# 03_ESP32.net
KiCad netlist of a schematic drawn in Altium Designer
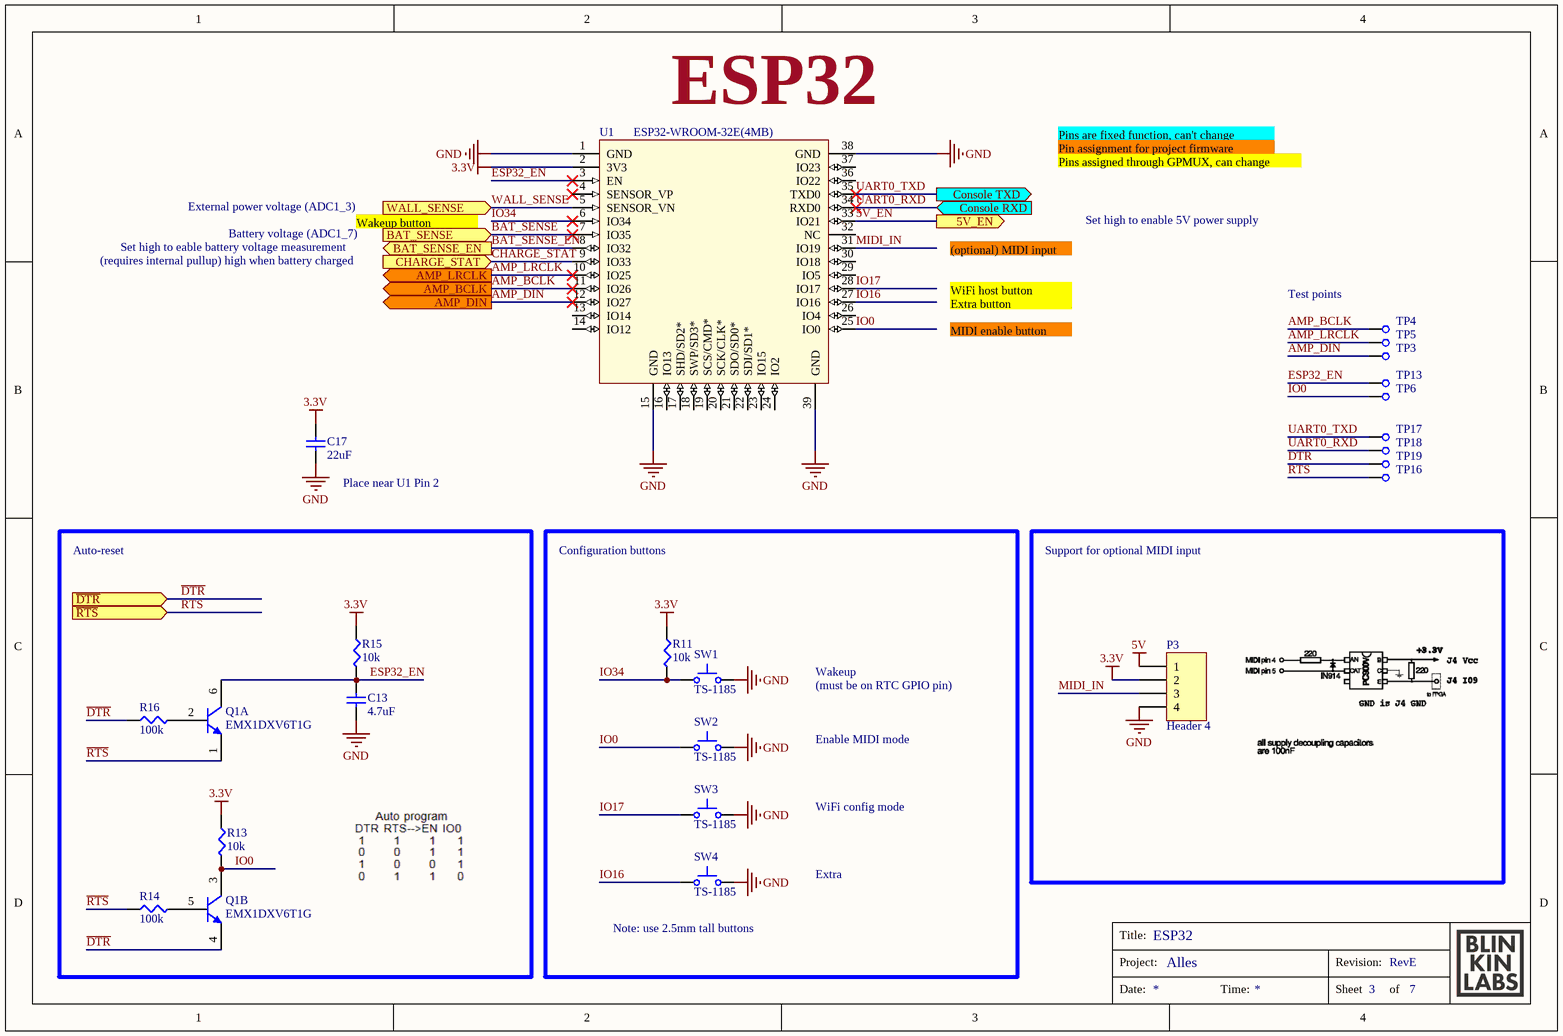
[diagram p0: [03] ESP32.SchDoc]

(export (version "E")
  (design (tool "Eeschema 10.0.6"))
  (components
    (comp (ref "C13")
      (value "4.7uF")
      (footprint "CAPC1608X09L")
      (description "CAP CER 4.7UF 10V X5R 0603")
      (fields
        (field (name "PARTNUMBER") "GRM185R61A475KE11D")
        (field (name "DIGI-KEY PART NUMBER") "490-11988-1-ND")
      )
      (libsource (lib "cap_murata") (part "CAPACITOR"))
    )
    (comp (ref "C17")
      (value "22uF")
      (footprint "CAPC1608X09L")
      (description "CAP CER 22UF 10V X5R 0603")
      (fields
        (field (name "PARTNUMBER") "GRM187R61A226ME15D")
        (field (name "DIGI-KEY PART NUMBER") "490-13243-1-ND")
      )
      (libsource (lib "cap_murata") (part "CAPACITOR"))
    )
    (comp (ref "P3")
      (value "Header 4")
      (footprint "HDR1X4")
      (description "Header, 4-Pin")
      (fields (field (name "PUBLISHER") "Altium Limited"))
      (libsource (lib "Miscellaneous Connectors") (part "Header 4"))
    )
    (comp (ref "Q1")
      (value "EMX1DXV6T1G")
      (footprint "ONSC-SOT-563-6-463A-01_V")
      (description "Dual NPN General Purpose Amplifier Transistors, 6-Pin SOT-563, Pb-Free, Tape and Reel")
      (fields (field (name "MANUFACTURER") "On Semiconductor"))
      (libsource (lib "Altium Content Vault") (part "ONSC-NPN_NPN-6_E"))
    )
    (comp (ref "R11")
      (value "10k")
      (footprint "ERJ2G(0402)_L")
      (description "RES SMD 10K OHM 5% 1/10W 0402")
      (fields (field (name "PARTNUMBER") "ERJ-2GEJ103X") (field (name "DIGI-KEY PART NUMBER") "P10KJCT-ND"))
      (libsource (lib "res_panasonic_erj_xls") (part "RESISTOR"))
    )
    (comp (ref "R13")
      (value "10k")
      (footprint "ERJ2G(0402)_L")
      (description "RES SMD 10K OHM 5% 1/10W 0402")
      (fields (field (name "PARTNUMBER") "ERJ-2GEJ103X") (field (name "DIGI-KEY PART NUMBER") "P10KJCT-ND"))
      (libsource (lib "res_panasonic_erj_xls") (part "RESISTOR"))
    )
    (comp (ref "R14")
      (value "100k")
      (footprint "ERJ2G(0402)_L")
      (description "RES SMD 100K OHM 5% 1/10W 0402")
      (fields (field (name "PARTNUMBER") "ERJ-2GEJ104X") (field (name "DIGI-KEY PART NUMBER") "P100KJCT-ND"))
      (libsource (lib "res_panasonic_erj_xls") (part "RESISTOR"))
    )
    (comp (ref "R15")
      (value "10k")
      (footprint "ERJ2G(0402)_L")
      (description "RES SMD 10K OHM 5% 1/10W 0402")
      (fields (field (name "PARTNUMBER") "ERJ-2GEJ103X") (field (name "DIGI-KEY PART NUMBER") "P10KJCT-ND"))
      (libsource (lib "res_panasonic_erj_xls") (part "RESISTOR"))
    )
    (comp (ref "R16")
      (value "100k")
      (footprint "ERJ2G(0402)_L")
      (description "RES SMD 100K OHM 5% 1/10W 0402")
      (fields (field (name "PARTNUMBER") "ERJ-2GEJ104X") (field (name "DIGI-KEY PART NUMBER") "P100KJCT-ND"))
      (libsource (lib "res_panasonic_erj_xls") (part "RESISTOR"))
    )
    (comp (ref "SW1")
      (value "TS-1185")
      (footprint "TS-1185")
      (description "Tact Switch, 3x4mm, no alignment pin, turtle style")
      (fields (field (name "MANUFACTURER") "XKB"))
      (libsource (lib "Blinkinlabs") (part "TS-1185"))
    )
    (comp (ref "SW2")
      (value "TS-1185")
      (footprint "TS-1185")
      (description "Tact Switch, 3x4mm, no alignment pin, turtle style")
      (fields (field (name "MANUFACTURER") "XKB"))
      (libsource (lib "Blinkinlabs") (part "TS-1185"))
    )
    (comp (ref "SW3")
      (value "TS-1185")
      (footprint "TS-1185")
      (description "Tact Switch, 3x4mm, no alignment pin, turtle style")
      (fields (field (name "MANUFACTURER") "XKB"))
      (libsource (lib "Blinkinlabs") (part "TS-1185"))
    )
    (comp (ref "SW4")
      (value "TS-1185")
      (footprint "TS-1185")
      (description "Tact Switch, 3x4mm, no alignment pin, turtle style")
      (fields (field (name "MANUFACTURER") "XKB"))
      (libsource (lib "Blinkinlabs") (part "TS-1185"))
    )
    (comp (ref "TP3")
      (value "TEST_POINT")
      (footprint "TP-SMD-1mm")
      (description "Test point")
      (libsource (lib "Blinkinlabs") (part "TEST_POINT"))
    )
    (comp (ref "TP4")
      (value "TEST_POINT")
      (footprint "TP-SMD-1mm")
      (description "Test point")
      (libsource (lib "Blinkinlabs") (part "TEST_POINT"))
    )
    (comp (ref "TP5")
      (value "TEST_POINT")
      (footprint "TP-SMD-1mm")
      (description "Test point")
      (libsource (lib "Blinkinlabs") (part "TEST_POINT"))
    )
    (comp (ref "TP6")
      (value "TEST_POINT")
      (footprint "TP-SMD-1mm")
      (description "Test point")
      (libsource (lib "Blinkinlabs") (part "TEST_POINT"))
    )
    (comp (ref "TP13")
      (value "TEST_POINT")
      (footprint "TP-SMD-1mm")
      (description "Test point")
      (libsource (lib "Blinkinlabs") (part "TEST_POINT"))
    )
    (comp (ref "TP16")
      (value "TEST_POINT")
      (footprint "TP-SMD-1mm")
      (description "Test point")
      (libsource (lib "Blinkinlabs") (part "TEST_POINT"))
    )
    (comp (ref "TP17")
      (value "TEST_POINT")
      (footprint "TP-SMD-1mm")
      (description "Test point")
      (libsource (lib "Blinkinlabs") (part "TEST_POINT"))
    )
    (comp (ref "TP18")
      (value "TEST_POINT")
      (footprint "TP-SMD-1mm")
      (description "Test point")
      (libsource (lib "Blinkinlabs") (part "TEST_POINT"))
    )
    (comp (ref "TP19")
      (value "TEST_POINT")
      (footprint "TP-SMD-1mm")
      (description "Test point")
      (libsource (lib "Blinkinlabs") (part "TEST_POINT"))
    )
    (comp (ref "U1")
      (value "ESP32-WROOM-32E(4MB)")
      (footprint "ESP32-WROOM-32-shortpad")
      (description "32-bit MCU & 2.4 GHz Wi-Fi & Bluetooth/Bluetooth LE")
      (fields (field (name "MANUFACTURER") "Espressif Systems") (field (name "LCSC PARTNUMBER") "C701341"))
      (libsource (lib "Blinkinlabs") (part "ESP32-WROOM-32E(4MB)"))
    )
  )
  (nets
    (net (code "1") (name "/5V_EN") (class "Default")
      (node (ref "U1") (pin "33") (pinfunction "IO21_33") (pintype "bidirectional"))
    )
    (net (code "2") (name "/AMP_BCLK") (class "Default")
      (node (ref "TP4") (pin "1") (pinfunction "TP_1") (pintype "passive"))
      (node (ref "U1") (pin "11") (pinfunction "IO26_11") (pintype "bidirectional"))
    )
    (net (code "3") (name "/AMP_DIN") (class "Default")
      (node (ref "TP3") (pin "1") (pinfunction "TP_1") (pintype "passive"))
      (node (ref "U1") (pin "12") (pinfunction "IO27_12") (pintype "bidirectional"))
    )
    (net (code "4") (name "/AMP_LRCLK") (class "Default")
      (node (ref "TP5") (pin "1") (pinfunction "TP_1") (pintype "passive"))
      (node (ref "U1") (pin "10") (pinfunction "IO25_10") (pintype "bidirectional"))
    )
    (net (code "5") (name "/BAT_SENSE") (class "Default")
      (node (ref "U1") (pin "7") (pinfunction "IO35_7") (pintype "input+no_connect"))
    )
    (net (code "6") (name "/BAT_SENSE_EN") (class "Default")
      (node (ref "U1") (pin "8") (pinfunction "IO32_8") (pintype "bidirectional"))
    )
    (net (code "7") (name "/CHARGE_STAT") (class "Default")
      (node (ref "U1") (pin "9") (pinfunction "IO33_9") (pintype "bidirectional"))
    )
    (net (code "8") (name "/ESP32_EN") (class "Default")
      (node (ref "C13") (pin "1") (pinfunction "1_1") (pintype "passive"))
      (node (ref "Q1") (pin "6") (pinfunction "C_6") (pintype "passive"))
      (node (ref "R15") (pin "2") (pinfunction "2_2") (pintype "passive"))
      (node (ref "TP13") (pin "1") (pinfunction "TP_1") (pintype "passive"))
      (node (ref "U1") (pin "3") (pinfunction "EN_3") (pintype "input"))
    )
    (net (code "9") (name "/IO0") (class "Default")
      (node (ref "Q1") (pin "3") (pinfunction "C_3") (pintype "passive"))
      (node (ref "R13") (pin "2") (pinfunction "2_2") (pintype "passive"))
      (node (ref "SW2") (pin "1") (pinfunction "1_1") (pintype "passive"))
      (node (ref "TP6") (pin "1") (pinfunction "TP_1") (pintype "passive"))
      (node (ref "U1") (pin "25") (pinfunction "IO0_25") (pintype "bidirectional"))
    )
    (net (code "10") (name "/IO16") (class "Default")
      (node (ref "SW4") (pin "1") (pinfunction "1_1") (pintype "passive"))
      (node (ref "U1") (pin "27") (pinfunction "IO16_27") (pintype "bidirectional"))
    )
    (net (code "11") (name "/IO17") (class "Default")
      (node (ref "SW3") (pin "1") (pinfunction "1_1") (pintype "passive"))
      (node (ref "U1") (pin "28") (pinfunction "IO17_28") (pintype "bidirectional"))
    )
    (net (code "12") (name "/IO34") (class "Default")
      (node (ref "R11") (pin "2") (pinfunction "2_2") (pintype "passive"))
      (node (ref "SW1") (pin "1") (pinfunction "1_1") (pintype "passive"))
      (node (ref "U1") (pin "6") (pinfunction "IO34_6") (pintype "input"))
    )
    (net (code "13") (name "/MIDI_IN") (class "Default")
      (node (ref "P3") (pin "3") (pinfunction "3_3") (pintype "passive"))
      (node (ref "U1") (pin "31") (pinfunction "IO19_31") (pintype "bidirectional"))
    )
    (net (code "14") (name "/UART0_RXD") (class "Default")
      (node (ref "TP18") (pin "1") (pinfunction "TP_1") (pintype "passive"))
      (node (ref "U1") (pin "34") (pinfunction "RXD0_34") (pintype "bidirectional"))
    )
    (net (code "15") (name "/UART0_TXD") (class "Default")
      (node (ref "TP17") (pin "1") (pinfunction "TP_1") (pintype "passive"))
      (node (ref "U1") (pin "35") (pinfunction "TXD0_35") (pintype "bidirectional"))
    )
    (net (code "16") (name "/WALL_SENSE") (class "Default")
      (node (ref "U1") (pin "5") (pinfunction "SENSOR_VN_5") (pintype "input"))
    )
    (net (code "17") (name "/~{DTR}") (class "Default")
      (node (ref "Q1") (pin "4") (pinfunction "E_4") (pintype "passive"))
      (node (ref "R16") (pin "1") (pinfunction "1_1") (pintype "passive"))
      (node (ref "TP19") (pin "1") (pinfunction "TP_1") (pintype "passive"))
    )
    (net (code "18") (name "/~{RTS}") (class "Default")
      (node (ref "Q1") (pin "1") (pinfunction "E_1") (pintype "passive"))
      (node (ref "R14") (pin "1") (pinfunction "1_1") (pintype "passive"))
      (node (ref "TP16") (pin "1") (pinfunction "TP_1") (pintype "passive"))
    )
    (net (code "19") (name "3.3V") (class "Default")
      (node (ref "C17") (pin "1") (pinfunction "1_1") (pintype "passive"))
      (node (ref "P3") (pin "2") (pinfunction "2_2") (pintype "passive"))
      (node (ref "R11") (pin "1") (pinfunction "1_1") (pintype "passive"))
      (node (ref "R13") (pin "1") (pinfunction "1_1") (pintype "passive"))
      (node (ref "R15") (pin "1") (pinfunction "1_1") (pintype "passive"))
      (node (ref "U1") (pin "2") (pinfunction "3V3_2") (pintype "power_in"))
    )
    (net (code "20") (name "5V") (class "Default")
      (node (ref "P3") (pin "1") (pinfunction "1_1") (pintype "passive"))
    )
    (net (code "21") (name "GND") (class "Default")
      (node (ref "C13") (pin "2") (pinfunction "2_2") (pintype "passive"))
      (node (ref "C17") (pin "2") (pinfunction "2_2") (pintype "passive"))
      (node (ref "P3") (pin "4") (pinfunction "4_4") (pintype "passive"))
      (node (ref "SW1") (pin "2") (pinfunction "2_2") (pintype "passive"))
      (node (ref "SW2") (pin "2") (pinfunction "2_2") (pintype "passive"))
      (node (ref "SW3") (pin "2") (pinfunction "2_2") (pintype "passive"))
      (node (ref "SW4") (pin "2") (pinfunction "2_2") (pintype "passive"))
      (node (ref "U1") (pin "1") (pinfunction "GND_1") (pintype "power_in"))
      (node (ref "U1") (pin "15") (pinfunction "GND_15") (pintype "power_in"))
      (node (ref "U1") (pin "38") (pinfunction "GND_38") (pintype "power_in"))
      (node (ref "U1") (pin "39") (pinfunction "GND_39") (pintype "power_in"))
    )
    (net (code "22") (name "Net-(Q1A-B)") (class "Default")
      (node (ref "Q1") (pin "2") (pinfunction "B_2") (pintype "passive"))
      (node (ref "R16") (pin "2") (pinfunction "2_2") (pintype "passive"))
    )
    (net (code "23") (name "Net-(Q1B-B)") (class "Default")
      (node (ref "Q1") (pin "5") (pinfunction "B_5") (pintype "passive"))
      (node (ref "R14") (pin "2") (pinfunction "2_2") (pintype "passive"))
    )
    (net (code "24") (name "unconnected-(U1-IO2-Pad24)") (class "Default")
      (node (ref "U1") (pin "24") (pinfunction "IO2_24") (pintype "bidirectional"))
    )
    (net (code "25") (name "unconnected-(U1-IO4-Pad26)") (class "Default")
      (node (ref "U1") (pin "26") (pinfunction "IO4_26") (pintype "bidirectional"))
    )
    (net (code "26") (name "unconnected-(U1-IO5-Pad29)") (class "Default")
      (node (ref "U1") (pin "29") (pinfunction "IO5_29") (pintype "bidirectional"))
    )
    (net (code "27") (name "unconnected-(U1-IO12-Pad14)") (class "Default")
      (node (ref "U1") (pin "14") (pinfunction "IO12_14") (pintype "bidirectional"))
    )
    (net (code "28") (name "unconnected-(U1-IO13-Pad16)") (class "Default")
      (node (ref "U1") (pin "16") (pinfunction "IO13_16") (pintype "bidirectional"))
    )
    (net (code "29") (name "unconnected-(U1-IO14-Pad13)") (class "Default")
      (node (ref "U1") (pin "13") (pinfunction "IO14_13") (pintype "bidirectional"))
    )
    (net (code "30") (name "unconnected-(U1-IO15-Pad23)") (class "Default")
      (node (ref "U1") (pin "23") (pinfunction "IO15_23") (pintype "bidirectional"))
    )
    (net (code "31") (name "unconnected-(U1-IO18-Pad30)") (class "Default")
      (node (ref "U1") (pin "30") (pinfunction "IO18_30") (pintype "bidirectional"))
    )
    (net (code "32") (name "unconnected-(U1-IO22-Pad36)") (class "Default")
      (node (ref "U1") (pin "36") (pinfunction "IO22_36") (pintype "bidirectional"))
    )
    (net (code "33") (name "unconnected-(U1-IO23-Pad37)") (class "Default")
      (node (ref "U1") (pin "37") (pinfunction "IO23_37") (pintype "bidirectional"))
    )
    (net (code "34") (name "unconnected-(U1-NC-Pad32)") (class "Default")
      (node (ref "U1") (pin "32") (pinfunction "NC_32") (pintype "passive"))
    )
    (net (code "35") (name "unconnected-(U1-SCK{slash}CLK*-Pad20)") (class "Default")
      (node (ref "U1") (pin "20") (pinfunction "SCK/CLK*_20") (pintype "bidirectional"))
    )
    (net (code "36") (name "unconnected-(U1-SCS{slash}CMD*-Pad19)") (class "Default")
      (node (ref "U1") (pin "19") (pinfunction "SCS/CMD*_19") (pintype "bidirectional"))
    )
    (net (code "37") (name "unconnected-(U1-SDI{slash}SD1*-Pad22)") (class "Default")
      (node (ref "U1") (pin "22") (pinfunction "SDI/SD1*_22") (pintype "bidirectional"))
    )
    (net (code "38") (name "unconnected-(U1-SDO{slash}SD0*-Pad21)") (class "Default")
      (node (ref "U1") (pin "21") (pinfunction "SDO/SD0*_21") (pintype "bidirectional"))
    )
    (net (code "39") (name "unconnected-(U1-SENSOR_VP-Pad4)") (class "Default")
      (node (ref "U1") (pin "4") (pinfunction "SENSOR_VP_4") (pintype "input+no_connect"))
    )
    (net (code "40") (name "unconnected-(U1-SHD{slash}SD2*-Pad17)") (class "Default")
      (node (ref "U1") (pin "17") (pinfunction "SHD/SD2*_17") (pintype "bidirectional"))
    )
    (net (code "41") (name "unconnected-(U1-SWP{slash}SD3*-Pad18)") (class "Default")
      (node (ref "U1") (pin "18") (pinfunction "SWP/SD3*_18") (pintype "bidirectional"))
    )
  )
)
